# vl4e3p.net
KiCad netlist of a schematic drawn in EAGLE
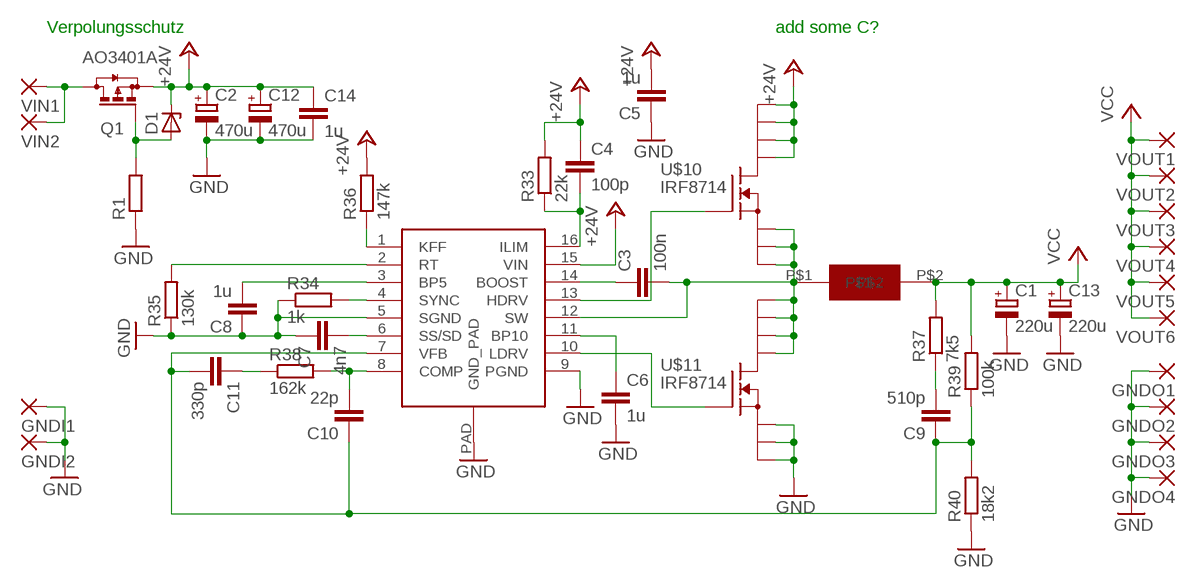
[diagram p0: schematic, sheet 1]

(export (version "E")
  (design (tool "Eeschema 10.0.6"))
  (components
    (comp (ref "C1")
      (value "220u")
      (footprint "eagle-import:E3,5-8")
      (libsource (lib "eagle-import") (part "CPOL-EUE3.5-8"))
    )
    (comp (ref "C2")
      (value "470u")
      (footprint "eagle-import:E3,5-8")
      (libsource (lib "eagle-import") (part "CPOL-EUE3.5-8"))
    )
    (comp (ref "C3")
      (value "100n")
      (footprint "eagle-import:C0805S")
      (libsource (lib "eagle-import") (part "C-EUC0805S"))
    )
    (comp (ref "C4")
      (value "100p")
      (footprint "eagle-import:C0805")
      (libsource (lib "eagle-import") (part "C-EUC0805"))
    )
    (comp (ref "C5")
      (value "1u")
      (footprint "eagle-import:C0805")
      (libsource (lib "eagle-import") (part "C-EUC0805"))
    )
    (comp (ref "C6")
      (value "1u")
      (footprint "eagle-import:C0805")
      (libsource (lib "eagle-import") (part "C-EUC0805"))
    )
    (comp (ref "C7")
      (value "4n7")
      (footprint "eagle-import:C0805")
      (libsource (lib "eagle-import") (part "C-EUC0805"))
    )
    (comp (ref "C8")
      (value "1u")
      (footprint "eagle-import:C0805")
      (libsource (lib "eagle-import") (part "C-EUC0805"))
    )
    (comp (ref "C9")
      (value "510p")
      (footprint "eagle-import:C0805")
      (libsource (lib "eagle-import") (part "C-EUC0805"))
    )
    (comp (ref "C10")
      (value "22p")
      (footprint "eagle-import:C0805")
      (libsource (lib "eagle-import") (part "C-EUC0805"))
    )
    (comp (ref "C11")
      (value "330p")
      (footprint "eagle-import:C0805")
      (libsource (lib "eagle-import") (part "C-EUC0805"))
    )
    (comp (ref "C12")
      (value "470u")
      (footprint "eagle-import:E3,5-8")
      (libsource (lib "eagle-import") (part "CPOL-EUE3.5-8"))
    )
    (comp (ref "C13")
      (value "220u")
      (footprint "eagle-import:E3,5-8")
      (libsource (lib "eagle-import") (part "CPOL-EUE3.5-8"))
    )
    (comp (ref "C14")
      (value "1u")
      (footprint "eagle-import:C0805")
      (libsource (lib "eagle-import") (part "C-EUC0805"))
    )
    (comp (ref "D1")
      (value "ZENER-DIODESOT23")
      (footprint "eagle-import:SOT23")
      (libsource (lib "eagle-import") (part "ZENER-DIODESOT23"))
    )
    (comp (ref "GNDI1")
      (value "PAD5-2,5")
      (footprint "eagle-import:5-2,5")
      (libsource (lib "eagle-import") (part "WIREPADSMD5-2,5"))
    )
    (comp (ref "GNDI2")
      (value "PAD5-2,5")
      (footprint "eagle-import:5-2,5")
      (libsource (lib "eagle-import") (part "WIREPADSMD5-2,5"))
    )
    (comp (ref "GNDO1")
      (value "PAD5-2,5")
      (footprint "eagle-import:5-2,5")
      (libsource (lib "eagle-import") (part "WIREPADSMD5-2,5"))
    )
    (comp (ref "GNDO2")
      (value "PAD5-2,5")
      (footprint "eagle-import:5-2,5")
      (libsource (lib "eagle-import") (part "WIREPADSMD5-2,5"))
    )
    (comp (ref "GNDO3")
      (value "PAD5-2,5")
      (footprint "eagle-import:5-2,5")
      (libsource (lib "eagle-import") (part "WIREPADSMD5-2,5"))
    )
    (comp (ref "GNDO4")
      (value "PAD5-2,5")
      (footprint "eagle-import:5-2,5")
      (libsource (lib "eagle-import") (part "WIREPADSMD5-2,5"))
    )
    (comp (ref "Q1")
      (value "AO3401A")
      (footprint "eagle-import:SOT23")
      (libsource (lib "eagle-import") (part "BSS84"))
    )
    (comp (ref "R1")
      (value "R-EU_R0805")
      (footprint "eagle-import:R0805")
      (libsource (lib "eagle-import") (part "R-EU_R0805"))
    )
    (comp (ref "R33")
      (value "22k")
      (footprint "eagle-import:R0805")
      (libsource (lib "eagle-import") (part "R-EU_R0805"))
    )
    (comp (ref "R34")
      (value "1k")
      (footprint "eagle-import:R0805")
      (libsource (lib "eagle-import") (part "R-EU_R0805"))
    )
    (comp (ref "R35")
      (value "130k")
      (footprint "eagle-import:R0805")
      (libsource (lib "eagle-import") (part "R-EU_R0805"))
    )
    (comp (ref "R36")
      (value "147k")
      (footprint "eagle-import:R0805")
      (libsource (lib "eagle-import") (part "R-EU_R0805"))
    )
    (comp (ref "R37")
      (value "7k5")
      (footprint "eagle-import:R0805")
      (libsource (lib "eagle-import") (part "R-EU_R0805"))
    )
    (comp (ref "R38")
      (value "162k")
      (footprint "eagle-import:R0805")
      (libsource (lib "eagle-import") (part "R-EU_R0805"))
    )
    (comp (ref "R39")
      (value "100k")
      (footprint "eagle-import:R0805")
      (libsource (lib "eagle-import") (part "R-EU_R0805"))
    )
    (comp (ref "R40")
      (value "18k2")
      (footprint "eagle-import:R0805")
      (libsource (lib "eagle-import") (part "R-EU_R0805"))
    )
    (comp (ref "U$1")
      (value "6u8")
      (footprint "eagle-import:FOO")
      (libsource (lib "eagle-import") (part "L"))
    )
    (comp (ref "U$9")
      (value "TPS40055")
      (footprint "eagle-import:TSSOP16")
      (libsource (lib "eagle-import") (part "TPS40055"))
    )
    (comp (ref "U$10")
      (value "IRF8714")
      (footprint "eagle-import:SO8")
      (libsource (lib "eagle-import") (part "IRF8714"))
    )
    (comp (ref "U$11")
      (value "IRF8714")
      (footprint "eagle-import:SO8")
      (libsource (lib "eagle-import") (part "IRF8714"))
    )
    (comp (ref "VIN1")
      (value "PAD5-2,5")
      (footprint "eagle-import:5-2,5")
      (libsource (lib "eagle-import") (part "WIREPADSMD5-2,5"))
    )
    (comp (ref "VIN2")
      (value "PAD5-2,5")
      (footprint "eagle-import:5-2,5")
      (libsource (lib "eagle-import") (part "WIREPADSMD5-2,5"))
    )
    (comp (ref "VOUT1")
      (value "PAD5-2,5")
      (footprint "eagle-import:5-2,5")
      (libsource (lib "eagle-import") (part "WIREPADSMD5-2,5"))
    )
    (comp (ref "VOUT2")
      (value "PAD5-2,5")
      (footprint "eagle-import:5-2,5")
      (libsource (lib "eagle-import") (part "WIREPADSMD5-2,5"))
    )
    (comp (ref "VOUT3")
      (value "PAD5-2,5")
      (footprint "eagle-import:5-2,5")
      (libsource (lib "eagle-import") (part "WIREPADSMD5-2,5"))
    )
    (comp (ref "VOUT4")
      (value "PAD5-2,5")
      (footprint "eagle-import:5-2,5")
      (libsource (lib "eagle-import") (part "WIREPADSMD5-2,5"))
    )
    (comp (ref "VOUT5")
      (value "PAD5-2,5")
      (footprint "eagle-import:5-2,5")
      (libsource (lib "eagle-import") (part "WIREPADSMD5-2,5"))
    )
    (comp (ref "VOUT6")
      (value "PAD5-2,5")
      (footprint "eagle-import:5-2,5")
      (libsource (lib "eagle-import") (part "WIREPADSMD5-2,5"))
    )
  )
  (nets
    (net (code "1") (name "+24V") (class "Default")
      (node (ref "C12") (pin "+") (pinfunction "+_+") (pintype "passive"))
      (node (ref "C14") (pin "1") (pinfunction "1_1") (pintype "passive"))
      (node (ref "C2") (pin "+") (pinfunction "+_+") (pintype "passive"))
      (node (ref "C4") (pin "1") (pinfunction "1_1") (pintype "passive"))
      (node (ref "C5") (pin "2") (pinfunction "2_2") (pintype "passive"))
      (node (ref "D1") (pin "3") (pinfunction "C_3") (pintype "passive"))
      (node (ref "Q1") (pin "2") (pinfunction "S_2") (pintype "passive"))
      (node (ref "R33") (pin "2") (pinfunction "2_2") (pintype "passive"))
      (node (ref "R36") (pin "2") (pinfunction "2_2") (pintype "passive"))
      (node (ref "U$10") (pin "5") (pinfunction "D_5") (pintype "passive"))
      (node (ref "U$10") (pin "6") (pinfunction "D_6") (pintype "passive"))
      (node (ref "U$10") (pin "7") (pinfunction "D_7") (pintype "passive"))
      (node (ref "U$10") (pin "8") (pinfunction "D_8") (pintype "passive"))
      (node (ref "U$9") (pin "15") (pinfunction "VIN_15") (pintype "bidirectional"))
    )
    (net (code "2") (name "GND") (class "Default")
      (node (ref "C1") (pin "-") (pinfunction "-_-") (pintype "passive"))
      (node (ref "C12") (pin "-") (pinfunction "-_-") (pintype "passive"))
      (node (ref "C13") (pin "-") (pinfunction "-_-") (pintype "passive"))
      (node (ref "C14") (pin "2") (pinfunction "2_2") (pintype "passive"))
      (node (ref "C2") (pin "-") (pinfunction "-_-") (pintype "passive"))
      (node (ref "C5") (pin "1") (pinfunction "1_1") (pintype "passive"))
      (node (ref "C6") (pin "2") (pinfunction "2_2") (pintype "passive"))
      (node (ref "C7") (pin "1") (pinfunction "1_1") (pintype "passive"))
      (node (ref "C8") (pin "1") (pinfunction "1_1") (pintype "passive"))
      (node (ref "GNDI1") (pin "1") (pinfunction "P_1") (pintype "passive"))
      (node (ref "GNDI2") (pin "1") (pinfunction "P_1") (pintype "passive"))
      (node (ref "GNDO1") (pin "1") (pinfunction "P_1") (pintype "passive"))
      (node (ref "GNDO2") (pin "1") (pinfunction "P_1") (pintype "passive"))
      (node (ref "GNDO3") (pin "1") (pinfunction "P_1") (pintype "passive"))
      (node (ref "GNDO4") (pin "1") (pinfunction "P_1") (pintype "passive"))
      (node (ref "R1") (pin "1") (pinfunction "1_1") (pintype "passive"))
      (node (ref "R34") (pin "1") (pinfunction "1_1") (pintype "passive"))
      (node (ref "R35") (pin "1") (pinfunction "1_1") (pintype "passive"))
      (node (ref "R40") (pin "1") (pinfunction "1_1") (pintype "passive"))
      (node (ref "U$11") (pin "1") (pinfunction "S_1") (pintype "passive"))
      (node (ref "U$11") (pin "2") (pinfunction "S_2") (pintype "passive"))
      (node (ref "U$11") (pin "3") (pinfunction "S_3") (pintype "passive"))
      (node (ref "U$9") (pin "5") (pinfunction "SGND_5") (pintype "bidirectional"))
      (node (ref "U$9") (pin "9") (pinfunction "PGND_9") (pintype "bidirectional"))
      (node (ref "U$9") (pin "PAD") (pinfunction "GND_PAD_PAD") (pintype "bidirectional"))
    )
    (net (code "3") (name "Net-(C9-Pad2)") (class "Default")
      (node (ref "C9") (pin "2") (pinfunction "2_2") (pintype "passive"))
      (node (ref "R37") (pin "1") (pinfunction "1_1") (pintype "passive"))
    )
    (net (code "4") (name "Net-(C11-Pad1)") (class "Default")
      (node (ref "C11") (pin "1") (pinfunction "1_1") (pintype "passive"))
      (node (ref "R38") (pin "1") (pinfunction "1_1") (pintype "passive"))
    )
    (net (code "5") (name "Net-(D1-A)") (class "Default")
      (node (ref "D1") (pin "1") (pinfunction "A_1") (pintype "passive"))
      (node (ref "Q1") (pin "1") (pinfunction "G_1") (pintype "passive"))
      (node (ref "R1") (pin "2") (pinfunction "2_2") (pintype "passive"))
    )
    (net (code "6") (name "Net-(Q1-D)") (class "Default")
      (node (ref "Q1") (pin "3") (pinfunction "D_3") (pintype "passive"))
      (node (ref "VIN1") (pin "1") (pinfunction "P_1") (pintype "passive"))
      (node (ref "VIN2") (pin "1") (pinfunction "P_1") (pintype "passive"))
    )
    (net (code "7") (name "Net-(U$9-BOOST)") (class "Default")
      (node (ref "C3") (pin "1") (pinfunction "1_1") (pintype "passive"))
      (node (ref "U$9") (pin "14") (pinfunction "BOOST_14") (pintype "bidirectional"))
    )
    (net (code "8") (name "Net-(U$9-BP5)") (class "Default")
      (node (ref "C8") (pin "2") (pinfunction "2_2") (pintype "passive"))
      (node (ref "U$9") (pin "3") (pinfunction "BP5_3") (pintype "bidirectional"))
    )
    (net (code "9") (name "Net-(U$9-BP10)") (class "Default")
      (node (ref "C6") (pin "1") (pinfunction "1_1") (pintype "passive"))
      (node (ref "U$9") (pin "11") (pinfunction "BP10_11") (pintype "bidirectional"))
    )
    (net (code "10") (name "Net-(U$9-COMP)") (class "Default")
      (node (ref "C10") (pin "2") (pinfunction "2_2") (pintype "passive"))
      (node (ref "R38") (pin "2") (pinfunction "2_2") (pintype "passive"))
      (node (ref "U$9") (pin "8") (pinfunction "COMP_8") (pintype "bidirectional"))
    )
    (net (code "11") (name "Net-(U$9-ILIM)") (class "Default")
      (node (ref "C4") (pin "2") (pinfunction "2_2") (pintype "passive"))
      (node (ref "R33") (pin "1") (pinfunction "1_1") (pintype "passive"))
      (node (ref "U$9") (pin "16") (pinfunction "ILIM_16") (pintype "bidirectional"))
    )
    (net (code "12") (name "Net-(U$9-KFF)") (class "Default")
      (node (ref "R36") (pin "1") (pinfunction "1_1") (pintype "passive"))
      (node (ref "U$9") (pin "1") (pinfunction "KFF_1") (pintype "bidirectional"))
    )
    (net (code "13") (name "Net-(U$9-RT)") (class "Default")
      (node (ref "R35") (pin "2") (pinfunction "2_2") (pintype "passive"))
      (node (ref "U$9") (pin "2") (pinfunction "RT_2") (pintype "bidirectional"))
    )
    (net (code "14") (name "Net-(U$9-SS{slash}SD)") (class "Default")
      (node (ref "C7") (pin "2") (pinfunction "2_2") (pintype "passive"))
      (node (ref "U$9") (pin "6") (pinfunction "SS/SD_6") (pintype "bidirectional"))
    )
    (net (code "15") (name "Net-(U$9-SW)") (class "Default")
      (node (ref "C3") (pin "2") (pinfunction "2_2") (pintype "passive"))
      (node (ref "U$1") (pin "P$1") (pinfunction "P$1_P$1") (pintype "bidirectional"))
      (node (ref "U$10") (pin "1") (pinfunction "S_1") (pintype "passive"))
      (node (ref "U$10") (pin "2") (pinfunction "S_2") (pintype "passive"))
      (node (ref "U$10") (pin "3") (pinfunction "S_3") (pintype "passive"))
      (node (ref "U$11") (pin "5") (pinfunction "D_5") (pintype "passive"))
      (node (ref "U$11") (pin "6") (pinfunction "D_6") (pintype "passive"))
      (node (ref "U$11") (pin "7") (pinfunction "D_7") (pintype "passive"))
      (node (ref "U$11") (pin "8") (pinfunction "D_8") (pintype "passive"))
      (node (ref "U$9") (pin "12") (pinfunction "SW_12") (pintype "bidirectional"))
    )
    (net (code "16") (name "Net-(U$9-SYNC)") (class "Default")
      (node (ref "R34") (pin "2") (pinfunction "2_2") (pintype "passive"))
      (node (ref "U$9") (pin "4") (pinfunction "SYNC_4") (pintype "bidirectional"))
    )
    (net (code "17") (name "Net-(U$9-VFB)") (class "Default")
      (node (ref "C10") (pin "1") (pinfunction "1_1") (pintype "passive"))
      (node (ref "C11") (pin "2") (pinfunction "2_2") (pintype "passive"))
      (node (ref "C9") (pin "1") (pinfunction "1_1") (pintype "passive"))
      (node (ref "R39") (pin "1") (pinfunction "1_1") (pintype "passive"))
      (node (ref "R40") (pin "2") (pinfunction "2_2") (pintype "passive"))
      (node (ref "U$9") (pin "7") (pinfunction "VFB_7") (pintype "bidirectional"))
    )
    (net (code "18") (name "Net-(U$10-G)") (class "Default")
      (node (ref "U$10") (pin "4") (pinfunction "G_4") (pintype "passive"))
      (node (ref "U$9") (pin "13") (pinfunction "HDRV_13") (pintype "bidirectional"))
    )
    (net (code "19") (name "Net-(U$11-G)") (class "Default")
      (node (ref "U$11") (pin "4") (pinfunction "G_4") (pintype "passive"))
      (node (ref "U$9") (pin "10") (pinfunction "LDRV_10") (pintype "bidirectional"))
    )
    (net (code "20") (name "VCC") (class "Default")
      (node (ref "C1") (pin "+") (pinfunction "+_+") (pintype "passive"))
      (node (ref "C13") (pin "+") (pinfunction "+_+") (pintype "passive"))
      (node (ref "R37") (pin "2") (pinfunction "2_2") (pintype "passive"))
      (node (ref "R39") (pin "2") (pinfunction "2_2") (pintype "passive"))
      (node (ref "U$1") (pin "P$2") (pinfunction "P$2_P$2") (pintype "bidirectional"))
      (node (ref "VOUT1") (pin "1") (pinfunction "P_1") (pintype "passive"))
      (node (ref "VOUT2") (pin "1") (pinfunction "P_1") (pintype "passive"))
      (node (ref "VOUT3") (pin "1") (pinfunction "P_1") (pintype "passive"))
      (node (ref "VOUT4") (pin "1") (pinfunction "P_1") (pintype "passive"))
      (node (ref "VOUT5") (pin "1") (pinfunction "P_1") (pintype "passive"))
      (node (ref "VOUT6") (pin "1") (pinfunction "P_1") (pintype "passive"))
    )
  )
)
